# papilio_cam_board.net
KiCad netlist of a schematic drawn in EAGLE
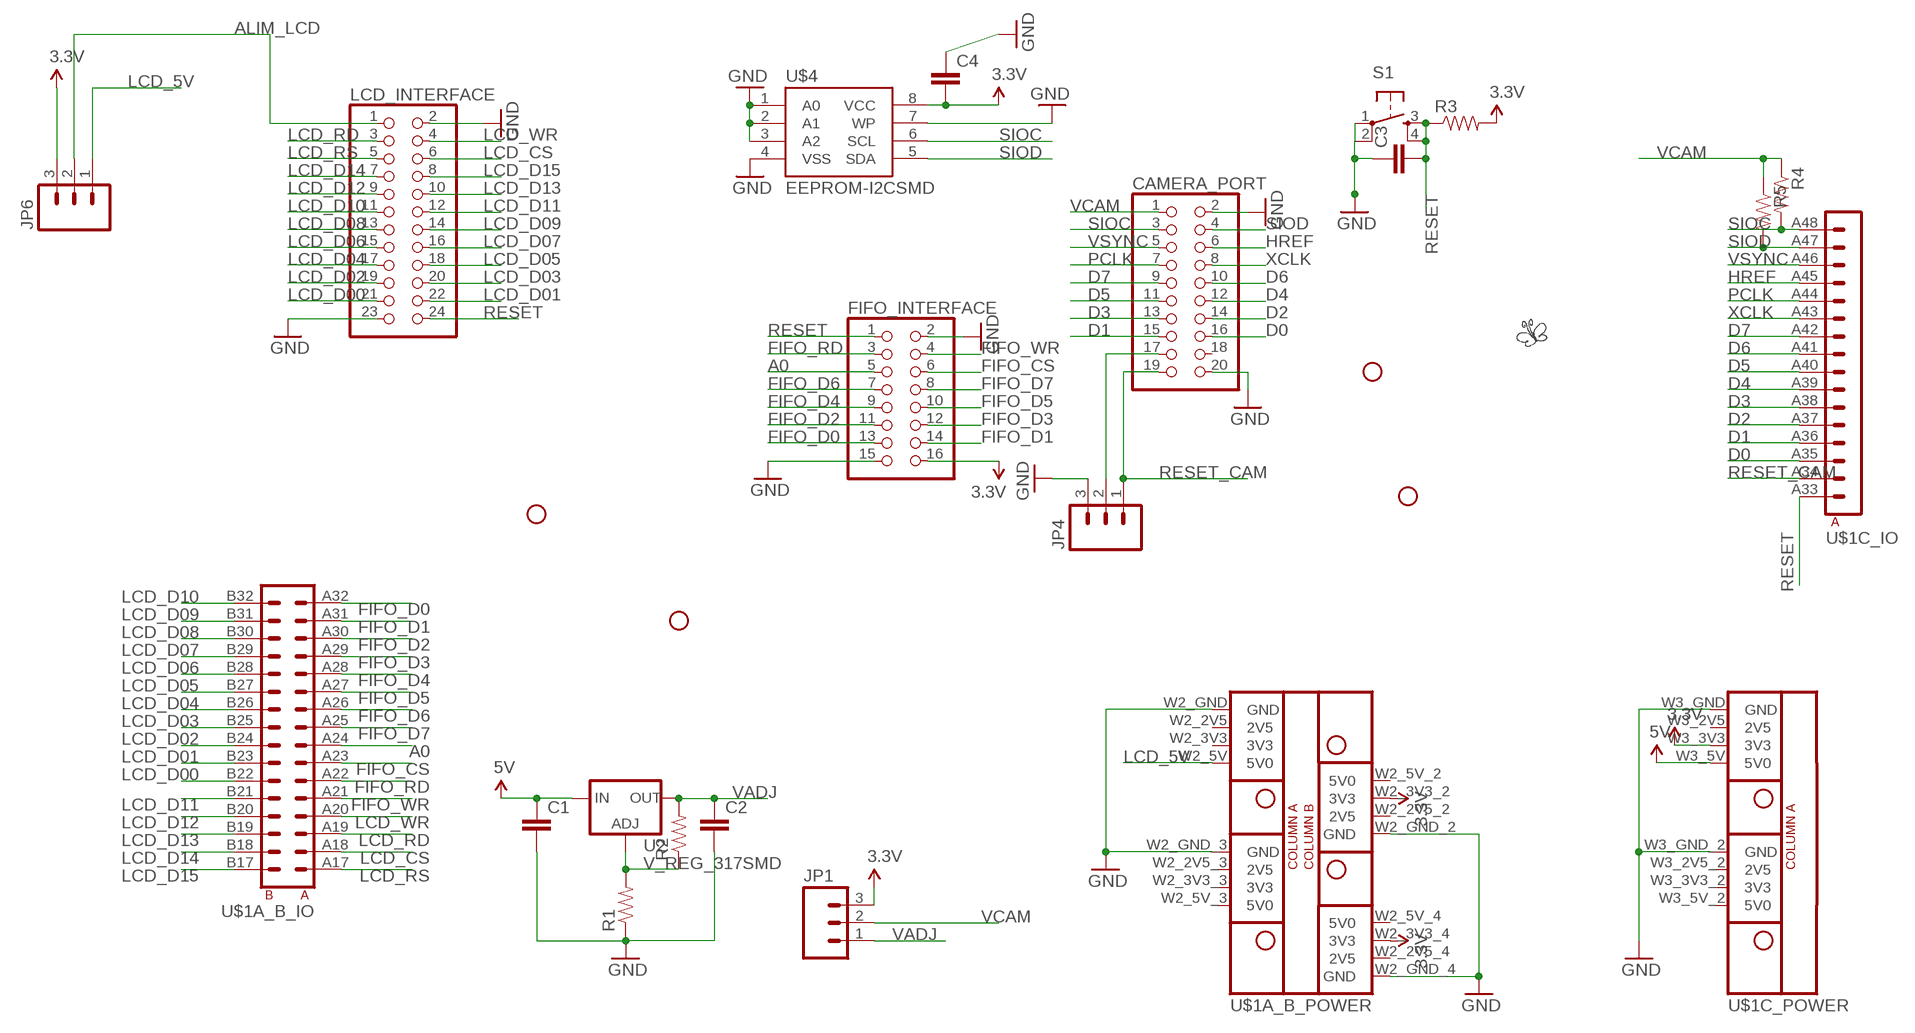
[diagram p0: schematic, sheet 1]

(export (version "E")
  (design (tool "Eeschema 10.0.6"))
  (components
    (comp (ref "C1")
      (value "CAP0805")
      (footprint "eagle-import:0805")
      (libsource (lib "eagle-import") (part "CAP0805"))
    )
    (comp (ref "C2")
      (value "CAP0805")
      (footprint "eagle-import:0805")
      (libsource (lib "eagle-import") (part "CAP0805"))
    )
    (comp (ref "C3")
      (value "CAP0805")
      (footprint "eagle-import:0805")
      (libsource (lib "eagle-import") (part "CAP0805"))
    )
    (comp (ref "C4")
      (value "CAP0805")
      (footprint "eagle-import:0805")
      (libsource (lib "eagle-import") (part "CAP0805"))
    )
    (comp (ref "CAMERA_PORT")
      (value "PINHD-2X10")
      (footprint "eagle-import:2X10")
      (libsource (lib "eagle-import") (part "PINHD-2X10"))
    )
    (comp (ref "FIFO_INTERFACE")
      (value "PINHD-2X8")
      (footprint "eagle-import:2X08")
      (libsource (lib "eagle-import") (part "PINHD-2X8"))
    )
    (comp (ref "JP1")
      (value "M03PTH")
      (footprint "eagle-import:1X03")
      (libsource (lib "eagle-import") (part "M03PTH"))
    )
    (comp (ref "JP2")
      (value "STAND-OFF")
      (footprint "eagle-import:STAND-OFF")
      (libsource (lib "eagle-import") (part "STAND-OFF"))
    )
    (comp (ref "JP3")
      (value "STAND-OFF")
      (footprint "eagle-import:STAND-OFF")
      (libsource (lib "eagle-import") (part "STAND-OFF"))
    )
    (comp (ref "JP4")
      (value "M03PTH")
      (footprint "eagle-import:1X03")
      (libsource (lib "eagle-import") (part "M03PTH"))
    )
    (comp (ref "JP5")
      (value "STAND-OFF")
      (footprint "eagle-import:STAND-OFF")
      (libsource (lib "eagle-import") (part "STAND-OFF"))
    )
    (comp (ref "JP6")
      (value "M03PTH")
      (footprint "eagle-import:1X03")
      (libsource (lib "eagle-import") (part "M03PTH"))
    )
    (comp (ref "JP7")
      (value "STAND-OFF")
      (footprint "eagle-import:STAND-OFF")
      (libsource (lib "eagle-import") (part "STAND-OFF"))
    )
    (comp (ref "LCD_INTERFACE")
      (value "PINHD-2X12")
      (footprint "eagle-import:2X12")
      (libsource (lib "eagle-import") (part "PINHD-2X12"))
    )
    (comp (ref "LOGO1")
      (value "BUTTERFLY_LOGO")
      (footprint "eagle-import:BUTTERFLY_LOGO")
      (libsource (lib "eagle-import") (part "BUTTERFLY_LOGO"))
    )
    (comp (ref "R1")
      (value "RESISTOR0805-RES")
      (footprint "eagle-import:0805")
      (libsource (lib "eagle-import") (part "RESISTOR0805-RES"))
    )
    (comp (ref "R2")
      (value "RESISTOR0805-RES")
      (footprint "eagle-import:0805")
      (libsource (lib "eagle-import") (part "RESISTOR0805-RES"))
    )
    (comp (ref "R3")
      (value "RESISTOR0805-RES")
      (footprint "eagle-import:0805")
      (libsource (lib "eagle-import") (part "RESISTOR0805-RES"))
    )
    (comp (ref "R4")
      (value "RESISTOR0805-RES")
      (footprint "eagle-import:0805")
      (libsource (lib "eagle-import") (part "RESISTOR0805-RES"))
    )
    (comp (ref "R5")
      (value "RESISTOR0805-RES")
      (footprint "eagle-import:0805")
      (libsource (lib "eagle-import") (part "RESISTOR0805-RES"))
    )
    (comp (ref "S1")
      (value "TAC_SWITCHSMD")
      (footprint "eagle-import:TACTILE_SWITCH_SMD")
      (libsource (lib "eagle-import") (part "TAC_SWITCHSMD"))
    )
    (comp (ref "U$1")
      (value "MEGAWING_FULL_P1MEGAWING_P1")
      (footprint "eagle-import:MEGAWING_FULL_NOHOLES_P1")
      (libsource (lib "eagle-import") (part "MEGAWING_FULL_P1MEGAWING_P1"))
    )
    (comp (ref "U$4")
      (value "EEPROM-I2CSMD")
      (footprint "eagle-import:SO08")
      (libsource (lib "eagle-import") (part "EEPROM-I2CSMD"))
    )
    (comp (ref "U2")
      (value "V_REG_317SMD")
      (footprint "eagle-import:SOT223")
      (libsource (lib "eagle-import") (part "V_REG_317SMD"))
    )
  )
  (nets
    (net (code "1") (name "/A0") (class "Default")
      (node (ref "FIFO_INTERFACE") (pin "5") (pinfunction "5_5") (pintype "passive"))
      (node (ref "U$1") (pin "A24") (pinfunction "A8_A24") (pintype "bidirectional"))
    )
    (net (code "2") (name "/ALIM_LCD") (class "Default")
      (node (ref "JP6") (pin "2") (pinfunction "2_2") (pintype "passive"))
      (node (ref "LCD_INTERFACE") (pin "1") (pinfunction "1_1") (pintype "passive"))
    )
    (net (code "3") (name "/D0") (class "Default")
      (node (ref "CAMERA_PORT") (pin "16") (pinfunction "16_16") (pintype "passive"))
      (node (ref "U$1") (pin "A35") (pinfunction "A3_A35") (pintype "bidirectional"))
    )
    (net (code "4") (name "/D1") (class "Default")
      (node (ref "CAMERA_PORT") (pin "15") (pinfunction "15_15") (pintype "passive"))
      (node (ref "U$1") (pin "A36") (pinfunction "A4_A36") (pintype "bidirectional"))
    )
    (net (code "5") (name "/D2") (class "Default")
      (node (ref "CAMERA_PORT") (pin "14") (pinfunction "14_14") (pintype "passive"))
      (node (ref "U$1") (pin "A37") (pinfunction "A5_A37") (pintype "bidirectional"))
    )
    (net (code "6") (name "/D3") (class "Default")
      (node (ref "CAMERA_PORT") (pin "13") (pinfunction "13_13") (pintype "passive"))
      (node (ref "U$1") (pin "A38") (pinfunction "A6_A38") (pintype "bidirectional"))
    )
    (net (code "7") (name "/D4") (class "Default")
      (node (ref "CAMERA_PORT") (pin "12") (pinfunction "12_12") (pintype "passive"))
      (node (ref "U$1") (pin "A39") (pinfunction "A7_A39") (pintype "bidirectional"))
    )
    (net (code "8") (name "/D5") (class "Default")
      (node (ref "CAMERA_PORT") (pin "11") (pinfunction "11_11") (pintype "passive"))
      (node (ref "U$1") (pin "A40") (pinfunction "A8_A40") (pintype "bidirectional"))
    )
    (net (code "9") (name "/D6") (class "Default")
      (node (ref "CAMERA_PORT") (pin "10") (pinfunction "10_10") (pintype "passive"))
      (node (ref "U$1") (pin "A41") (pinfunction "A9_A41") (pintype "bidirectional"))
    )
    (net (code "10") (name "/D7") (class "Default")
      (node (ref "CAMERA_PORT") (pin "9") (pinfunction "9_9") (pintype "passive"))
      (node (ref "U$1") (pin "A42") (pinfunction "A10_A42") (pintype "bidirectional"))
    )
    (net (code "11") (name "/FIFO_CS") (class "Default")
      (node (ref "FIFO_INTERFACE") (pin "6") (pinfunction "6_6") (pintype "passive"))
      (node (ref "U$1") (pin "A23") (pinfunction "A7_A23") (pintype "bidirectional"))
    )
    (net (code "12") (name "/FIFO_D0") (class "Default")
      (node (ref "FIFO_INTERFACE") (pin "13") (pinfunction "13_13") (pintype "passive"))
      (node (ref "U$1") (pin "A32") (pinfunction "A16_A32") (pintype "bidirectional"))
    )
    (net (code "13") (name "/FIFO_D1") (class "Default")
      (node (ref "FIFO_INTERFACE") (pin "14") (pinfunction "14_14") (pintype "passive"))
      (node (ref "U$1") (pin "A31") (pinfunction "A15_A31") (pintype "bidirectional"))
    )
    (net (code "14") (name "/FIFO_D2") (class "Default")
      (node (ref "FIFO_INTERFACE") (pin "11") (pinfunction "11_11") (pintype "passive"))
      (node (ref "U$1") (pin "A30") (pinfunction "A14_A30") (pintype "bidirectional"))
    )
    (net (code "15") (name "/FIFO_D3") (class "Default")
      (node (ref "FIFO_INTERFACE") (pin "12") (pinfunction "12_12") (pintype "passive"))
      (node (ref "U$1") (pin "A29") (pinfunction "A13_A29") (pintype "bidirectional"))
    )
    (net (code "16") (name "/FIFO_D4") (class "Default")
      (node (ref "FIFO_INTERFACE") (pin "9") (pinfunction "9_9") (pintype "passive"))
      (node (ref "U$1") (pin "A28") (pinfunction "A12_A28") (pintype "bidirectional"))
    )
    (net (code "17") (name "/FIFO_D5") (class "Default")
      (node (ref "FIFO_INTERFACE") (pin "10") (pinfunction "10_10") (pintype "passive"))
      (node (ref "U$1") (pin "A27") (pinfunction "A11_A27") (pintype "bidirectional"))
    )
    (net (code "18") (name "/FIFO_D6") (class "Default")
      (node (ref "FIFO_INTERFACE") (pin "7") (pinfunction "7_7") (pintype "passive"))
      (node (ref "U$1") (pin "A26") (pinfunction "A10_A26") (pintype "bidirectional"))
    )
    (net (code "19") (name "/FIFO_D7") (class "Default")
      (node (ref "FIFO_INTERFACE") (pin "8") (pinfunction "8_8") (pintype "passive"))
      (node (ref "U$1") (pin "A25") (pinfunction "A9_A25") (pintype "bidirectional"))
    )
    (net (code "20") (name "/FIFO_RD") (class "Default")
      (node (ref "FIFO_INTERFACE") (pin "3") (pinfunction "3_3") (pintype "passive"))
      (node (ref "U$1") (pin "A22") (pinfunction "A6_A22") (pintype "bidirectional"))
    )
    (net (code "21") (name "/FIFO_WR") (class "Default")
      (node (ref "FIFO_INTERFACE") (pin "4") (pinfunction "4_4") (pintype "passive"))
      (node (ref "U$1") (pin "A21") (pinfunction "A5_A21") (pintype "bidirectional"))
    )
    (net (code "22") (name "/HREF") (class "Default")
      (node (ref "CAMERA_PORT") (pin "6") (pinfunction "6_6") (pintype "passive"))
      (node (ref "U$1") (pin "A45") (pinfunction "A13_A45") (pintype "bidirectional"))
    )
    (net (code "23") (name "/LCD_5V") (class "Default")
      (node (ref "JP6") (pin "1") (pinfunction "1_1") (pintype "passive"))
      (node (ref "U$1") (pin "W2_5V") (pinfunction "5V0_W2_5V") (pintype "passive"))
    )
    (net (code "24") (name "/LCD_CS") (class "Default")
      (node (ref "LCD_INTERFACE") (pin "6") (pinfunction "6_6") (pintype "passive"))
      (node (ref "U$1") (pin "A18") (pinfunction "A2_A18") (pintype "bidirectional"))
    )
    (net (code "25") (name "/LCD_D00") (class "Default")
      (node (ref "LCD_INTERFACE") (pin "21") (pinfunction "21_21") (pintype "passive"))
      (node (ref "U$1") (pin "B22") (pinfunction "B6_B22") (pintype "bidirectional"))
    )
    (net (code "26") (name "/LCD_D01") (class "Default")
      (node (ref "LCD_INTERFACE") (pin "22") (pinfunction "22_22") (pintype "passive"))
      (node (ref "U$1") (pin "B23") (pinfunction "B7_B23") (pintype "bidirectional"))
    )
    (net (code "27") (name "/LCD_D02") (class "Default")
      (node (ref "LCD_INTERFACE") (pin "19") (pinfunction "19_19") (pintype "passive"))
      (node (ref "U$1") (pin "B24") (pinfunction "B8_B24") (pintype "bidirectional"))
    )
    (net (code "28") (name "/LCD_D03") (class "Default")
      (node (ref "LCD_INTERFACE") (pin "20") (pinfunction "20_20") (pintype "passive"))
      (node (ref "U$1") (pin "B25") (pinfunction "B9_B25") (pintype "bidirectional"))
    )
    (net (code "29") (name "/LCD_D04") (class "Default")
      (node (ref "LCD_INTERFACE") (pin "17") (pinfunction "17_17") (pintype "passive"))
      (node (ref "U$1") (pin "B26") (pinfunction "B10_B26") (pintype "bidirectional"))
    )
    (net (code "30") (name "/LCD_D05") (class "Default")
      (node (ref "LCD_INTERFACE") (pin "18") (pinfunction "18_18") (pintype "passive"))
      (node (ref "U$1") (pin "B27") (pinfunction "B11_B27") (pintype "bidirectional"))
    )
    (net (code "31") (name "/LCD_D06") (class "Default")
      (node (ref "LCD_INTERFACE") (pin "15") (pinfunction "15_15") (pintype "passive"))
      (node (ref "U$1") (pin "B28") (pinfunction "B12_B28") (pintype "bidirectional"))
    )
    (net (code "32") (name "/LCD_D07") (class "Default")
      (node (ref "LCD_INTERFACE") (pin "16") (pinfunction "16_16") (pintype "passive"))
      (node (ref "U$1") (pin "B29") (pinfunction "B13_B29") (pintype "bidirectional"))
    )
    (net (code "33") (name "/LCD_D08") (class "Default")
      (node (ref "LCD_INTERFACE") (pin "13") (pinfunction "13_13") (pintype "passive"))
      (node (ref "U$1") (pin "B30") (pinfunction "B14_B30") (pintype "bidirectional"))
    )
    (net (code "34") (name "/LCD_D09") (class "Default")
      (node (ref "LCD_INTERFACE") (pin "14") (pinfunction "14_14") (pintype "passive"))
      (node (ref "U$1") (pin "B31") (pinfunction "B15_B31") (pintype "bidirectional"))
    )
    (net (code "35") (name "/LCD_D10") (class "Default")
      (node (ref "LCD_INTERFACE") (pin "11") (pinfunction "11_11") (pintype "passive"))
      (node (ref "U$1") (pin "B32") (pinfunction "B16_B32") (pintype "bidirectional"))
    )
    (net (code "36") (name "/LCD_D11") (class "Default")
      (node (ref "LCD_INTERFACE") (pin "12") (pinfunction "12_12") (pintype "passive"))
      (node (ref "U$1") (pin "B21") (pinfunction "B5_B21") (pintype "bidirectional"))
    )
    (net (code "37") (name "/LCD_D12") (class "Default")
      (node (ref "LCD_INTERFACE") (pin "9") (pinfunction "9_9") (pintype "passive"))
      (node (ref "U$1") (pin "B20") (pinfunction "B4_B20") (pintype "bidirectional"))
    )
    (net (code "38") (name "/LCD_D13") (class "Default")
      (node (ref "LCD_INTERFACE") (pin "10") (pinfunction "10_10") (pintype "passive"))
      (node (ref "U$1") (pin "B19") (pinfunction "B3_B19") (pintype "bidirectional"))
    )
    (net (code "39") (name "/LCD_D14") (class "Default")
      (node (ref "LCD_INTERFACE") (pin "7") (pinfunction "7_7") (pintype "passive"))
      (node (ref "U$1") (pin "B18") (pinfunction "B2_B18") (pintype "bidirectional"))
    )
    (net (code "40") (name "/LCD_D15") (class "Default")
      (node (ref "LCD_INTERFACE") (pin "8") (pinfunction "8_8") (pintype "passive"))
      (node (ref "U$1") (pin "B17") (pinfunction "B1_B17") (pintype "bidirectional"))
    )
    (net (code "41") (name "/LCD_RD") (class "Default")
      (node (ref "LCD_INTERFACE") (pin "3") (pinfunction "3_3") (pintype "passive"))
      (node (ref "U$1") (pin "A19") (pinfunction "A3_A19") (pintype "bidirectional"))
    )
    (net (code "42") (name "/LCD_RS") (class "Default")
      (node (ref "LCD_INTERFACE") (pin "5") (pinfunction "5_5") (pintype "passive"))
      (node (ref "U$1") (pin "A17") (pinfunction "A1_A17") (pintype "bidirectional"))
    )
    (net (code "43") (name "/LCD_WR") (class "Default")
      (node (ref "LCD_INTERFACE") (pin "4") (pinfunction "4_4") (pintype "passive"))
      (node (ref "U$1") (pin "A20") (pinfunction "A4_A20") (pintype "bidirectional"))
    )
    (net (code "44") (name "/PCLK") (class "Default")
      (node (ref "CAMERA_PORT") (pin "7") (pinfunction "7_7") (pintype "passive"))
      (node (ref "U$1") (pin "A44") (pinfunction "A12_A44") (pintype "bidirectional"))
    )
    (net (code "45") (name "/RESET") (class "Default")
      (node (ref "C3") (pin "2") (pinfunction "2_2") (pintype "passive"))
      (node (ref "FIFO_INTERFACE") (pin "1") (pinfunction "1_1") (pintype "passive"))
      (node (ref "LCD_INTERFACE") (pin "24") (pinfunction "24_24") (pintype "passive"))
      (node (ref "R3") (pin "1") (pinfunction "1_1") (pintype "passive"))
      (node (ref "S1") (pin "3") (pinfunction "3_3") (pintype "passive"))
      (node (ref "S1") (pin "4") (pinfunction "4_4") (pintype "passive"))
      (node (ref "U$1") (pin "A33") (pinfunction "A1_A33") (pintype "bidirectional"))
    )
    (net (code "46") (name "/RESET_CAM") (class "Default")
      (node (ref "CAMERA_PORT") (pin "19") (pinfunction "19_19") (pintype "passive"))
      (node (ref "JP4") (pin "1") (pinfunction "1_1") (pintype "passive"))
      (node (ref "U$1") (pin "A34") (pinfunction "A2_A34") (pintype "bidirectional"))
    )
    (net (code "47") (name "/SIOC") (class "Default")
      (node (ref "CAMERA_PORT") (pin "3") (pinfunction "3_3") (pintype "passive"))
      (node (ref "R4") (pin "2") (pinfunction "2_2") (pintype "passive"))
      (node (ref "U$1") (pin "A48") (pinfunction "A16_A48") (pintype "bidirectional"))
      (node (ref "U$4") (pin "6") (pinfunction "SCL_6") (pintype "bidirectional"))
    )
    (net (code "48") (name "/SIOD") (class "Default")
      (node (ref "CAMERA_PORT") (pin "4") (pinfunction "4_4") (pintype "passive"))
      (node (ref "R5") (pin "2") (pinfunction "2_2") (pintype "passive"))
      (node (ref "U$1") (pin "A47") (pinfunction "A15_A47") (pintype "bidirectional"))
      (node (ref "U$4") (pin "5") (pinfunction "SDA_5") (pintype "bidirectional"))
    )
    (net (code "49") (name "/VADJ") (class "Default")
      (node (ref "C2") (pin "1") (pinfunction "1_1") (pintype "passive"))
      (node (ref "JP1") (pin "1") (pinfunction "1_1") (pintype "passive"))
      (node (ref "R2") (pin "2") (pinfunction "2_2") (pintype "passive"))
      (node (ref "U2") (pin "2") (pinfunction "OUT_2") (pintype "output"))
    )
    (net (code "50") (name "/VCAM") (class "Default")
      (node (ref "CAMERA_PORT") (pin "1") (pinfunction "1_1") (pintype "passive"))
      (node (ref "JP1") (pin "2") (pinfunction "2_2") (pintype "passive"))
      (node (ref "R4") (pin "1") (pinfunction "1_1") (pintype "passive"))
      (node (ref "R5") (pin "1") (pinfunction "1_1") (pintype "passive"))
    )
    (net (code "51") (name "/VSYNC") (class "Default")
      (node (ref "CAMERA_PORT") (pin "5") (pinfunction "5_5") (pintype "passive"))
      (node (ref "U$1") (pin "A46") (pinfunction "A14_A46") (pintype "bidirectional"))
    )
    (net (code "52") (name "/XCLK") (class "Default")
      (node (ref "CAMERA_PORT") (pin "8") (pinfunction "8_8") (pintype "passive"))
      (node (ref "U$1") (pin "A43") (pinfunction "A11_A43") (pintype "bidirectional"))
    )
    (net (code "53") (name "3.3V") (class "Default")
      (node (ref "C4") (pin "2") (pinfunction "2_2") (pintype "passive"))
      (node (ref "FIFO_INTERFACE") (pin "16") (pinfunction "16_16") (pintype "passive"))
      (node (ref "JP1") (pin "3") (pinfunction "3_3") (pintype "passive"))
      (node (ref "JP6") (pin "3") (pinfunction "3_3") (pintype "passive"))
      (node (ref "R3") (pin "2") (pinfunction "2_2") (pintype "passive"))
      (node (ref "U$1") (pin "W2_3V3_2") (pinfunction "3V3_W2_3V3_2") (pintype "passive"))
      (node (ref "U$1") (pin "W2_3V3_4") (pinfunction "3V3_W2_3V3_4") (pintype "passive"))
      (node (ref "U$1") (pin "W3_3V3") (pinfunction "3V3_W3_3V3") (pintype "passive"))
      (node (ref "U$4") (pin "8") (pinfunction "VCC_8") (pintype "power_in"))
    )
    (net (code "54") (name "5V") (class "Default")
      (node (ref "C1") (pin "1") (pinfunction "1_1") (pintype "passive"))
      (node (ref "U$1") (pin "W3_5V") (pinfunction "5V0_W3_5V") (pintype "passive"))
      (node (ref "U2") (pin "3") (pinfunction "IN_3") (pintype "input"))
    )
    (net (code "55") (name "GND") (class "Default")
      (node (ref "C1") (pin "2") (pinfunction "2_2") (pintype "passive"))
      (node (ref "C2") (pin "2") (pinfunction "2_2") (pintype "passive"))
      (node (ref "C3") (pin "1") (pinfunction "1_1") (pintype "passive"))
      (node (ref "C4") (pin "1") (pinfunction "1_1") (pintype "passive"))
      (node (ref "CAMERA_PORT") (pin "2") (pinfunction "2_2") (pintype "passive"))
      (node (ref "CAMERA_PORT") (pin "20") (pinfunction "20_20") (pintype "passive"))
      (node (ref "FIFO_INTERFACE") (pin "15") (pinfunction "15_15") (pintype "passive"))
      (node (ref "FIFO_INTERFACE") (pin "2") (pinfunction "2_2") (pintype "passive"))
      (node (ref "JP4") (pin "3") (pinfunction "3_3") (pintype "passive"))
      (node (ref "LCD_INTERFACE") (pin "2") (pinfunction "2_2") (pintype "passive"))
      (node (ref "LCD_INTERFACE") (pin "23") (pinfunction "23_23") (pintype "passive"))
      (node (ref "R1") (pin "1") (pinfunction "1_1") (pintype "passive"))
      (node (ref "S1") (pin "1") (pinfunction "1_1") (pintype "passive"))
      (node (ref "S1") (pin "2") (pinfunction "2_2") (pintype "passive"))
      (node (ref "U$1") (pin "W2_GND") (pinfunction "GND_W2_GND") (pintype "power_in"))
      (node (ref "U$1") (pin "W2_GND_2") (pinfunction "GND_W2_GND_2") (pintype "power_in"))
      (node (ref "U$1") (pin "W2_GND_3") (pinfunction "GND_W2_GND_3") (pintype "power_in"))
      (node (ref "U$1") (pin "W2_GND_4") (pinfunction "GND_W2_GND_4") (pintype "power_in"))
      (node (ref "U$1") (pin "W3_GND") (pinfunction "GND_W3_GND") (pintype "power_in"))
      (node (ref "U$1") (pin "W3_GND_2") (pinfunction "GND_W3_GND_2") (pintype "power_in"))
      (node (ref "U$4") (pin "1") (pinfunction "A0_1") (pintype "bidirectional"))
      (node (ref "U$4") (pin "2") (pinfunction "A1_2") (pintype "bidirectional"))
      (node (ref "U$4") (pin "3") (pinfunction "A2_3") (pintype "bidirectional"))
      (node (ref "U$4") (pin "4") (pinfunction "VSS_4") (pintype "power_in"))
      (node (ref "U$4") (pin "7") (pinfunction "WP_7") (pintype "bidirectional"))
    )
    (net (code "56") (name "Net-(CAMERA_PORT-Pad17)") (class "Default")
      (node (ref "CAMERA_PORT") (pin "17") (pinfunction "17_17") (pintype "passive"))
      (node (ref "JP4") (pin "2") (pinfunction "2_2") (pintype "passive"))
    )
    (net (code "57") (name "Net-(U2-ADJ)") (class "Default")
      (node (ref "R1") (pin "2") (pinfunction "2_2") (pintype "passive"))
      (node (ref "R2") (pin "1") (pinfunction "1_1") (pintype "passive"))
      (node (ref "U2") (pin "1") (pinfunction "ADJ_1") (pintype "input"))
    )
    (net (code "58") (name "unconnected-(CAMERA_PORT-Pad18)") (class "Default")
      (node (ref "CAMERA_PORT") (pin "18") (pinfunction "18_18") (pintype "passive"))
    )
    (net (code "59") (name "unconnected-(U$1B-2V5-PadW2_2V5)") (class "Default")
      (node (ref "U$1") (pin "W2_2V5") (pinfunction "2V5_W2_2V5") (pintype "passive"))
    )
    (net (code "60") (name "unconnected-(U$1B-2V5-PadW2_2V5_2)") (class "Default")
      (node (ref "U$1") (pin "W2_2V5_2") (pinfunction "2V5_W2_2V5_2") (pintype "passive"))
    )
    (net (code "61") (name "unconnected-(U$1B-2V5-PadW2_2V5_3)") (class "Default")
      (node (ref "U$1") (pin "W2_2V5_3") (pinfunction "2V5_W2_2V5_3") (pintype "passive"))
    )
    (net (code "62") (name "unconnected-(U$1B-2V5-PadW2_2V5_4)") (class "Default")
      (node (ref "U$1") (pin "W2_2V5_4") (pinfunction "2V5_W2_2V5_4") (pintype "passive"))
    )
    (net (code "63") (name "unconnected-(U$1B-3V3-PadW2_3V3)") (class "Default")
      (node (ref "U$1") (pin "W2_3V3") (pinfunction "3V3_W2_3V3") (pintype "passive"))
    )
    (net (code "64") (name "unconnected-(U$1B-3V3-PadW2_3V3_3)") (class "Default")
      (node (ref "U$1") (pin "W2_3V3_3") (pinfunction "3V3_W2_3V3_3") (pintype "passive"))
    )
    (net (code "65") (name "unconnected-(U$1B-5V0-PadW2_5V_2)") (class "Default")
      (node (ref "U$1") (pin "W2_5V_2") (pinfunction "5V0_W2_5V_2") (pintype "passive"))
    )
    (net (code "66") (name "unconnected-(U$1B-5V0-PadW2_5V_3)") (class "Default")
      (node (ref "U$1") (pin "W2_5V_3") (pinfunction "5V0_W2_5V_3") (pintype "passive"))
    )
    (net (code "67") (name "unconnected-(U$1B-5V0-PadW2_5V_4)") (class "Default")
      (node (ref "U$1") (pin "W2_5V_4") (pinfunction "5V0_W2_5V_4") (pintype "passive"))
    )
    (net (code "68") (name "unconnected-(U$1D-2V5-PadW3_2V5)") (class "Default")
      (node (ref "U$1") (pin "W3_2V5") (pinfunction "2V5_W3_2V5") (pintype "passive"))
    )
    (net (code "69") (name "unconnected-(U$1D-2V5-PadW3_2V5_2)") (class "Default")
      (node (ref "U$1") (pin "W3_2V5_2") (pinfunction "2V5_W3_2V5_2") (pintype "passive"))
    )
    (net (code "70") (name "unconnected-(U$1D-3V3-PadW3_3V3_2)") (class "Default")
      (node (ref "U$1") (pin "W3_3V3_2") (pinfunction "3V3_W3_3V3_2") (pintype "passive"))
    )
    (net (code "71") (name "unconnected-(U$1D-5V0-PadW3_5V_2)") (class "Default")
      (node (ref "U$1") (pin "W3_5V_2") (pinfunction "5V0_W3_5V_2") (pintype "passive"))
    )
  )
)
